# MODULE_PWR.net
KiCad netlist of a schematic drawn in Altium Designer
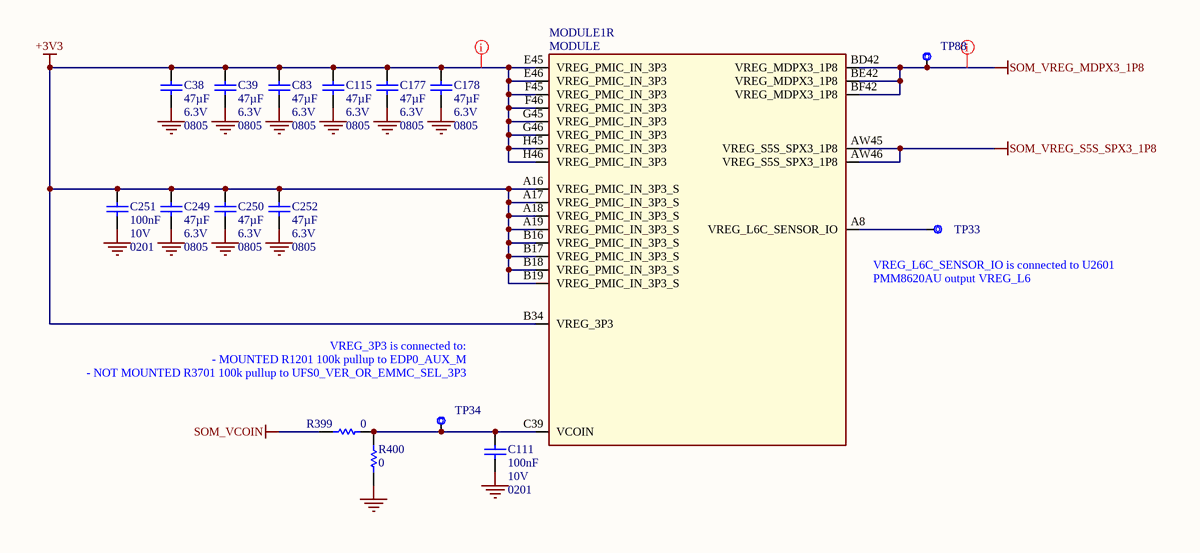
[diagram p0: MODULE_PWR.SchDoc]

(export (version "E")
  (design (tool "Eeschema 10.0.6"))
  (components
    (comp (ref "C38")
      (value "47µF")
      (footprint "CAP-0805")
      (description "CAP CHIP 0805 47uF 20% 6.3V X5R")
      (fields
        (field (name "PART NUMBER") "C0805C476M9PAC7800")
        (field (name "VOLTAGE") "6.3V")
        (field (name "MANUFACTURER") "KEMET")
        (field (name "CASE CODE (IMPERIAL)") "0805")
      )
      (libsource (lib "Clean") (part "CAP"))
    )
    (comp (ref "C39")
      (value "47µF")
      (footprint "CAP-0805")
      (description "CAP CHIP 0805 47uF 20% 6.3V X5R")
      (fields
        (field (name "PART NUMBER") "C0805C476M9PAC7800")
        (field (name "VOLTAGE") "6.3V")
        (field (name "MANUFACTURER") "KEMET")
        (field (name "CASE CODE (IMPERIAL)") "0805")
      )
      (libsource (lib "Clean") (part "CAP"))
    )
    (comp (ref "C83")
      (value "47µF")
      (footprint "CAP-0805")
      (description "CAP CHIP 0805 47uF 20% 6.3V X5R")
      (fields
        (field (name "PART NUMBER") "C0805C476M9PAC7800")
        (field (name "VOLTAGE") "6.3V")
        (field (name "MANUFACTURER") "KEMET")
        (field (name "CASE CODE (IMPERIAL)") "0805")
      )
      (libsource (lib "Clean") (part "CAP"))
    )
    (comp (ref "C111")
      (value "100nF")
      (footprint "CAP-0201")
      (description "CAP CHIP 0201 100nF 10% 10V X5R")
      (fields
        (field (name "PART NUMBER") "CL03A104KP3NNNC")
        (field (name "MANUFACTURER") "Samsung Electro-Mechanics")
        (field (name "VOLTAGE") "10V")
        (field (name "CASE CODE (IMPERIAL)") "0201")
      )
      (libsource (lib "Clean") (part "CAP"))
    )
    (comp (ref "C115")
      (value "47µF")
      (footprint "CAP-0805")
      (description "CAP CHIP 0805 47uF 20% 6.3V X5R")
      (fields
        (field (name "PART NUMBER") "C0805C476M9PAC7800")
        (field (name "VOLTAGE") "6.3V")
        (field (name "MANUFACTURER") "KEMET")
        (field (name "CASE CODE (IMPERIAL)") "0805")
      )
      (libsource (lib "Clean") (part "CAP"))
    )
    (comp (ref "C177")
      (value "47µF")
      (footprint "CAP-0805")
      (description "CAP CHIP 0805 47uF 20% 6.3V X5R")
      (fields
        (field (name "PART NUMBER") "C0805C476M9PAC7800")
        (field (name "VOLTAGE") "6.3V")
        (field (name "MANUFACTURER") "KEMET")
        (field (name "CASE CODE (IMPERIAL)") "0805")
      )
      (libsource (lib "Clean") (part "CAP"))
    )
    (comp (ref "C178")
      (value "47µF")
      (footprint "CAP-0805")
      (description "CAP CHIP 0805 47uF 20% 6.3V X5R")
      (fields
        (field (name "PART NUMBER") "C0805C476M9PAC7800")
        (field (name "VOLTAGE") "6.3V")
        (field (name "MANUFACTURER") "KEMET")
        (field (name "CASE CODE (IMPERIAL)") "0805")
      )
      (libsource (lib "Clean") (part "CAP"))
    )
    (comp (ref "C249")
      (value "47µF")
      (footprint "CAP-0805")
      (description "CAP CHIP 0805 47uF 20% 6.3V X5R")
      (fields
        (field (name "PART NUMBER") "C0805C476M9PAC7800")
        (field (name "VOLTAGE") "6.3V")
        (field (name "MANUFACTURER") "KEMET")
        (field (name "CASE CODE (IMPERIAL)") "0805")
      )
      (libsource (lib "Clean") (part "CAP"))
    )
    (comp (ref "C250")
      (value "47µF")
      (footprint "CAP-0805")
      (description "CAP CHIP 0805 47uF 20% 6.3V X5R")
      (fields
        (field (name "PART NUMBER") "C0805C476M9PAC7800")
        (field (name "VOLTAGE") "6.3V")
        (field (name "MANUFACTURER") "KEMET")
        (field (name "CASE CODE (IMPERIAL)") "0805")
      )
      (libsource (lib "Clean") (part "CAP"))
    )
    (comp (ref "C251")
      (value "100nF")
      (footprint "CAP-0201")
      (description "CAP CHIP 0201 100nF 10% 10V X5R")
      (fields
        (field (name "PART NUMBER") "CL03A104KP3NNNC")
        (field (name "MANUFACTURER") "Samsung Electro-Mechanics")
        (field (name "VOLTAGE") "10V")
        (field (name "CASE CODE (IMPERIAL)") "0201")
      )
      (libsource (lib "Clean") (part "CAP"))
    )
    (comp (ref "C252")
      (value "47µF")
      (footprint "CAP-0805")
      (description "CAP CHIP 0805 47uF 20% 6.3V X5R")
      (fields
        (field (name "PART NUMBER") "C0805C476M9PAC7800")
        (field (name "VOLTAGE") "6.3V")
        (field (name "MANUFACTURER") "KEMET")
        (field (name "CASE CODE (IMPERIAL)") "0805")
      )
      (libsource (lib "Clean") (part "CAP"))
    )
    (comp (ref "MODULE1")
      (value "MODULE")
      (footprint "MODULE")
      (description "MODULE BGA 1883 balls 57.5x57.5mm")
      (fields (field (name "MANUFACTURER") "Qualcomm") (field (name "PART NUMBER") "MODULE BGA"))
      (libsource (lib "Clean") (part "MODULE"))
    )
    (comp (ref "R399")
      (value "0")
      (footprint "RES-0201")
      (description "RES CHIP 0201 0R")
      (fields (field (name "MANUFACTURER") "Vishay") (field (name "PART NUMBER") "CRCW02010000Z0ED"))
      (libsource (lib "Clean") (part "RES"))
    )
    (comp (ref "R400")
      (value "0")
      (footprint "RES-0201")
      (description "RES CHIP 0201 0R")
      (fields (field (name "MANUFACTURER") "Vishay") (field (name "PART NUMBER") "CRCW02010000Z0ED"))
      (libsource (lib "Clean") (part "RES"))
    )
    (comp (ref "TP33")
      (value "Test point 1.00mm")
      (footprint "TP-1.00MM")
      (fields (field (name "PART NUMBER") "This is not a component"))
      (libsource (lib "Clean") (part "TESTPOINT"))
    )
    (comp (ref "TP34")
      (value "Test point 1.00mm")
      (footprint "TP-1.00MM")
      (fields (field (name "PART NUMBER") "This is not a component"))
      (libsource (lib "Clean") (part "TESTPOINT"))
    )
    (comp (ref "TP88")
      (value "Test point 1.00mm")
      (footprint "TP-1.00MM")
      (fields (field (name "PART NUMBER") "This is not a component"))
      (libsource (lib "Clean") (part "TESTPOINT"))
    )
  )
  (nets
    (net (code "1") (name "+3V3") (class "Default")
      (node (ref "C115") (pin "2") (pinfunction "2_2") (pintype "passive"))
      (node (ref "C177") (pin "2") (pinfunction "2_2") (pintype "passive"))
      (node (ref "C178") (pin "2") (pinfunction "2_2") (pintype "passive"))
      (node (ref "C249") (pin "2") (pinfunction "2_2") (pintype "passive"))
      (node (ref "C250") (pin "2") (pinfunction "2_2") (pintype "passive"))
      (node (ref "C251") (pin "2") (pinfunction "2_2") (pintype "passive"))
      (node (ref "C252") (pin "2") (pinfunction "2_2") (pintype "passive"))
      (node (ref "C38") (pin "2") (pinfunction "2_2") (pintype "passive"))
      (node (ref "C39") (pin "2") (pinfunction "2_2") (pintype "passive"))
      (node (ref "C83") (pin "2") (pinfunction "2_2") (pintype "passive"))
      (node (ref "MODULE1") (pin "A16") (pinfunction "VREG_PMIC_IN_3P3_S_A16") (pintype "passive"))
      (node (ref "MODULE1") (pin "A17") (pinfunction "VREG_PMIC_IN_3P3_S_A17") (pintype "passive"))
      (node (ref "MODULE1") (pin "A18") (pinfunction "VREG_PMIC_IN_3P3_S_A18") (pintype "passive"))
      (node (ref "MODULE1") (pin "A19") (pinfunction "VREG_PMIC_IN_3P3_S_A19") (pintype "passive"))
      (node (ref "MODULE1") (pin "B16") (pinfunction "VREG_PMIC_IN_3P3_S_B16") (pintype "passive"))
      (node (ref "MODULE1") (pin "B17") (pinfunction "VREG_PMIC_IN_3P3_S_B17") (pintype "passive"))
      (node (ref "MODULE1") (pin "B18") (pinfunction "VREG_PMIC_IN_3P3_S_B18") (pintype "passive"))
      (node (ref "MODULE1") (pin "B19") (pinfunction "VREG_PMIC_IN_3P3_S_B19") (pintype "passive"))
      (node (ref "MODULE1") (pin "B34") (pinfunction "VREG_3P3_B34") (pintype "passive"))
      (node (ref "MODULE1") (pin "E45") (pinfunction "VREG_PMIC_IN_3P3_E45") (pintype "passive"))
      (node (ref "MODULE1") (pin "E46") (pinfunction "VREG_PMIC_IN_3P3_E46") (pintype "passive"))
      (node (ref "MODULE1") (pin "F45") (pinfunction "VREG_PMIC_IN_3P3_F45") (pintype "passive"))
      (node (ref "MODULE1") (pin "F46") (pinfunction "VREG_PMIC_IN_3P3_F46") (pintype "passive"))
      (node (ref "MODULE1") (pin "G45") (pinfunction "VREG_PMIC_IN_3P3_G45") (pintype "passive"))
      (node (ref "MODULE1") (pin "G46") (pinfunction "VREG_PMIC_IN_3P3_G46") (pintype "passive"))
      (node (ref "MODULE1") (pin "H45") (pinfunction "VREG_PMIC_IN_3P3_H45") (pintype "passive"))
      (node (ref "MODULE1") (pin "H46") (pinfunction "VREG_PMIC_IN_3P3_H46") (pintype "passive"))
    )
    (net (code "2") (name "GND") (class "Default")
      (node (ref "C111") (pin "1") (pinfunction "1_1") (pintype "passive"))
      (node (ref "C115") (pin "1") (pinfunction "1_1") (pintype "passive"))
      (node (ref "C177") (pin "1") (pinfunction "1_1") (pintype "passive"))
      (node (ref "C178") (pin "1") (pinfunction "1_1") (pintype "passive"))
      (node (ref "C249") (pin "1") (pinfunction "1_1") (pintype "passive"))
      (node (ref "C250") (pin "1") (pinfunction "1_1") (pintype "passive"))
      (node (ref "C251") (pin "1") (pinfunction "1_1") (pintype "passive"))
      (node (ref "C252") (pin "1") (pinfunction "1_1") (pintype "passive"))
      (node (ref "C38") (pin "1") (pinfunction "1_1") (pintype "passive"))
      (node (ref "C39") (pin "1") (pinfunction "1_1") (pintype "passive"))
      (node (ref "C83") (pin "1") (pinfunction "1_1") (pintype "passive"))
      (node (ref "R400") (pin "1") (pinfunction "1_1") (pintype "passive"))
    )
    (net (code "3") (name "Net-(MODULE1R-VCOIN)") (class "Default")
      (node (ref "C111") (pin "2") (pinfunction "2_2") (pintype "passive"))
      (node (ref "MODULE1") (pin "C39") (pinfunction "VCOIN_C39") (pintype "passive"))
      (node (ref "R399") (pin "2") (pinfunction "2_2") (pintype "passive"))
      (node (ref "R400") (pin "2") (pinfunction "2_2") (pintype "passive"))
      (node (ref "TP34") (pin "X") (pinfunction "X_X") (pintype "passive"))
    )
    (net (code "4") (name "Net-(MODULE1R-VREG_L6C_SENSOR_IO)") (class "Default")
      (node (ref "MODULE1") (pin "A8") (pinfunction "VREG_L6C_SENSOR_IO_A8") (pintype "passive"))
      (node (ref "TP33") (pin "X") (pinfunction "X_X") (pintype "passive"))
    )
    (net (code "5") (name "SOM_VCOIN") (class "Default")
      (node (ref "R399") (pin "1") (pinfunction "1_1") (pintype "passive"))
    )
    (net (code "6") (name "SOM_VREG_MDPX3_1P8") (class "Default")
      (node (ref "MODULE1") (pin "BD42") (pinfunction "VREG_MDPX3_1P8_BD42") (pintype "passive"))
      (node (ref "MODULE1") (pin "BE42") (pinfunction "VREG_MDPX3_1P8_BE42") (pintype "passive"))
      (node (ref "MODULE1") (pin "BF42") (pinfunction "VREG_MDPX3_1P8_BF42") (pintype "passive"))
      (node (ref "TP88") (pin "X") (pinfunction "X_X") (pintype "passive"))
    )
    (net (code "7") (name "SOM_VREG_S5S_SPX3_1P8") (class "Default")
      (node (ref "MODULE1") (pin "AW45") (pinfunction "VREG_S5S_SPX3_1P8_AW45") (pintype "passive"))
      (node (ref "MODULE1") (pin "AW46") (pinfunction "VREG_S5S_SPX3_1P8_AW46") (pintype "passive"))
    )
  )
)
